# v4_a.net
KiCad netlist of a schematic drawn in EasyEDA Pro
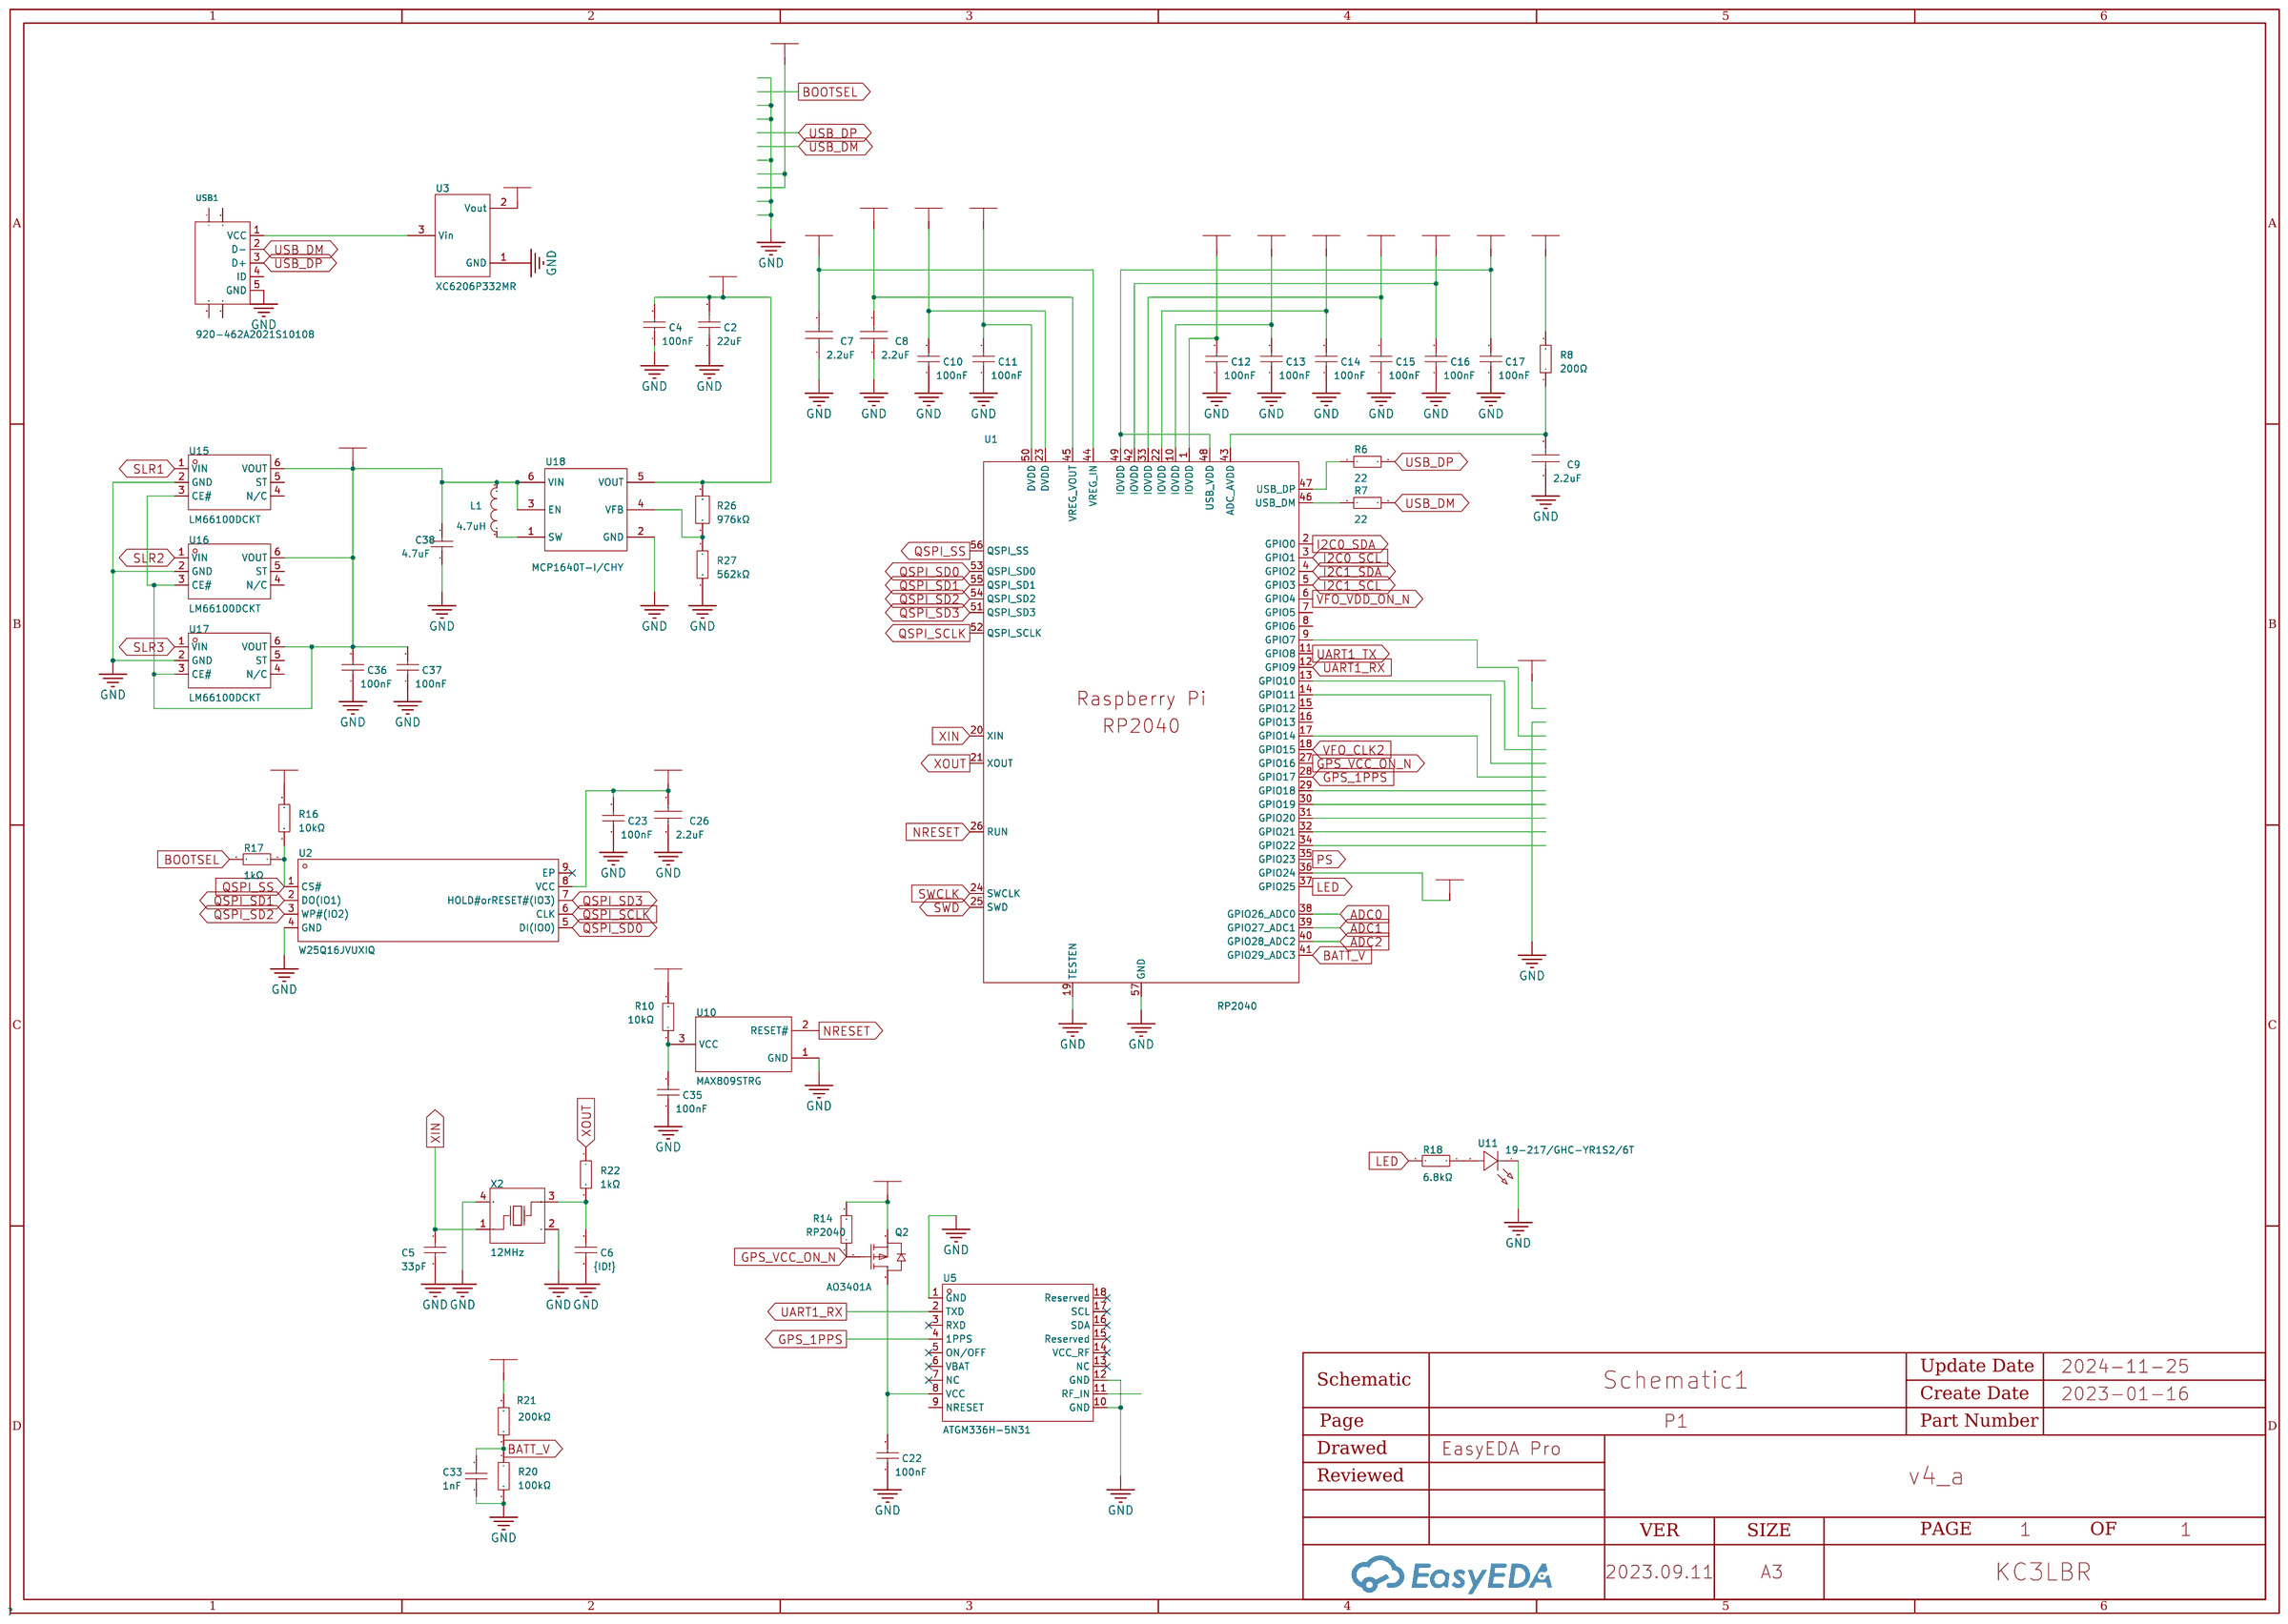
[diagram p0: schematic sheet]

(export (version "E")
  (design (tool "Eeschema 10.0.6"))
  (components
    (comp (ref "C2")
      (value "22uF")
      (footprint "easyedapro:C0603")
      (fields
        (field (name "Manufacturer Part") "CL10A226MQ8NRNC")
        (field (name "Manufacturer") "SAMSUNG(三星)")
      )
      (libsource (lib "easyedapro") (part "CL10A226MQ8NRNC"))
    )
    (comp (ref "C4")
      (value "100nF")
      (footprint "easyedapro:C0402_NEW")
      (fields
        (field (name "Manufacturer Part") "CL05B104KO5NNNC")
        (field (name "Manufacturer") "SAMSUNG(三星)")
      )
      (libsource (lib "easyedapro") (part "CL05B104KO5NNNC"))
    )
    (comp (ref "C5")
      (value "33pF")
      (footprint "easyedapro:C0402")
      (fields (field (name "Manufacturer Part") "0402CG330J500NT") (field (name "Manufacturer") "FH(风华)"))
      (libsource (lib "easyedapro") (part "0402CG330J500NT"))
    )
    (comp (ref "C6")
      (value "33pF")
      (footprint "easyedapro:C0402")
      (fields (field (name "Manufacturer Part") "0402CG330J500NT") (field (name "Manufacturer") "FH(风华)"))
      (libsource (lib "easyedapro") (part "0402CG330J500NT"))
    )
    (comp (ref "C7")
      (value "2.2uF")
      (footprint "easyedapro:C0402")
      (fields
        (field (name "Manufacturer Part") "CL05A225MQ5NSNC")
        (field (name "Manufacturer") "SAMSUNG(三星)")
      )
      (libsource (lib "easyedapro") (part "CL05A225MQ5NSNC"))
    )
    (comp (ref "C8")
      (value "2.2uF")
      (footprint "easyedapro:C0402")
      (fields
        (field (name "Manufacturer Part") "CL05A225MQ5NSNC")
        (field (name "Manufacturer") "SAMSUNG(三星)")
      )
      (libsource (lib "easyedapro") (part "CL05A225MQ5NSNC"))
    )
    (comp (ref "C9")
      (value "2.2uF")
      (footprint "easyedapro:C0402")
      (fields
        (field (name "Manufacturer Part") "CL05A225MQ5NSNC")
        (field (name "Manufacturer") "SAMSUNG(三星)")
      )
      (libsource (lib "easyedapro") (part "CL05A225MQ5NSNC"))
    )
    (comp (ref "C10")
      (value "100nF")
      (footprint "easyedapro:C0402_NEW")
      (fields
        (field (name "Manufacturer Part") "CL05B104KO5NNNC")
        (field (name "Manufacturer") "SAMSUNG(三星)")
      )
      (libsource (lib "easyedapro") (part "CL05B104KO5NNNC"))
    )
    (comp (ref "C11")
      (value "100nF")
      (footprint "easyedapro:C0402_NEW")
      (fields
        (field (name "Manufacturer Part") "CL05B104KO5NNNC")
        (field (name "Manufacturer") "SAMSUNG(三星)")
      )
      (libsource (lib "easyedapro") (part "CL05B104KO5NNNC"))
    )
    (comp (ref "C12")
      (value "100nF")
      (footprint "easyedapro:C0402_NEW")
      (fields
        (field (name "Manufacturer Part") "CL05B104KO5NNNC")
        (field (name "Manufacturer") "SAMSUNG(三星)")
      )
      (libsource (lib "easyedapro") (part "CL05B104KO5NNNC"))
    )
    (comp (ref "C13")
      (value "100nF")
      (footprint "easyedapro:C0402_NEW")
      (fields
        (field (name "Manufacturer Part") "CL05B104KO5NNNC")
        (field (name "Manufacturer") "SAMSUNG(三星)")
      )
      (libsource (lib "easyedapro") (part "CL05B104KO5NNNC"))
    )
    (comp (ref "C14")
      (value "100nF")
      (footprint "easyedapro:C0402_NEW")
      (fields
        (field (name "Manufacturer Part") "CL05B104KO5NNNC")
        (field (name "Manufacturer") "SAMSUNG(三星)")
      )
      (libsource (lib "easyedapro") (part "CL05B104KO5NNNC"))
    )
    (comp (ref "C15")
      (value "100nF")
      (footprint "easyedapro:C0402_NEW")
      (fields
        (field (name "Manufacturer Part") "CL05B104KO5NNNC")
        (field (name "Manufacturer") "SAMSUNG(三星)")
      )
      (libsource (lib "easyedapro") (part "CL05B104KO5NNNC"))
    )
    (comp (ref "C16")
      (value "100nF")
      (footprint "easyedapro:C0402_NEW")
      (fields
        (field (name "Manufacturer Part") "CL05B104KO5NNNC")
        (field (name "Manufacturer") "SAMSUNG(三星)")
      )
      (libsource (lib "easyedapro") (part "CL05B104KO5NNNC"))
    )
    (comp (ref "C17")
      (value "100nF")
      (footprint "easyedapro:C0402_NEW")
      (fields
        (field (name "Manufacturer Part") "CL05B104KO5NNNC")
        (field (name "Manufacturer") "SAMSUNG(三星)")
      )
      (libsource (lib "easyedapro") (part "CL05B104KO5NNNC"))
    )
    (comp (ref "C22")
      (value "100nF")
      (footprint "easyedapro:C0402_NEW")
      (fields
        (field (name "Manufacturer Part") "CL05B104KO5NNNC")
        (field (name "Manufacturer") "SAMSUNG(三星)")
      )
      (libsource (lib "easyedapro") (part "CL05B104KO5NNNC"))
    )
    (comp (ref "C23")
      (value "100nF")
      (footprint "easyedapro:C0402_NEW")
      (fields
        (field (name "Manufacturer Part") "CL05B104KO5NNNC")
        (field (name "Manufacturer") "SAMSUNG(三星)")
      )
      (libsource (lib "easyedapro") (part "CL05B104KO5NNNC"))
    )
    (comp (ref "C26")
      (value "2.2uF")
      (footprint "easyedapro:C0402")
      (fields
        (field (name "Manufacturer Part") "CL05A225MQ5NSNC")
        (field (name "Manufacturer") "SAMSUNG(三星)")
      )
      (libsource (lib "easyedapro") (part "CL05A225MQ5NSNC"))
    )
    (comp (ref "C33")
      (value "1nF")
      (footprint "easyedapro:C0402")
      (fields (field (name "Manufacturer Part") "0402B102K500NT") (field (name "Manufacturer") "FH(风华)"))
      (libsource (lib "easyedapro") (part "0402B102K500NT"))
    )
    (comp (ref "C35")
      (value "100nF")
      (footprint "easyedapro:C0402_NEW")
      (fields
        (field (name "Manufacturer Part") "CL05B104KO5NNNC")
        (field (name "Manufacturer") "SAMSUNG(三星)")
      )
      (libsource (lib "easyedapro") (part "CL05B104KO5NNNC"))
    )
    (comp (ref "C36")
      (value "100nF")
      (footprint "easyedapro:C0402_NEW")
      (fields
        (field (name "Manufacturer Part") "CL05B104KO5NNNC")
        (field (name "Manufacturer") "SAMSUNG(三星)")
      )
      (libsource (lib "easyedapro") (part "CL05B104KO5NNNC"))
    )
    (comp (ref "C37")
      (value "100nF")
      (footprint "easyedapro:C0402_NEW")
      (fields
        (field (name "Manufacturer Part") "CL05B104KO5NNNC")
        (field (name "Manufacturer") "SAMSUNG(三星)")
      )
      (libsource (lib "easyedapro") (part "CL05B104KO5NNNC"))
    )
    (comp (ref "C38")
      (value "4.7uF")
      (footprint "easyedapro:C0603")
      (fields
        (field (name "Manufacturer Part") "CL10A475KO8NNNC")
        (field (name "Manufacturer") "SAMSUNG(三星)")
      )
      (libsource (lib "easyedapro") (part "CL10A475KO8NNNC"))
    )
    (comp (ref "L1")
      (value "4.7uH")
      (footprint "easyedapro:IND-SMD_L2.5-W1.8")
      (fields
        (field (name "Manufacturer Part") "CBC2518T4R7M")
        (field (name "Manufacturer") "TAIYO YUDEN(太诱)")
      )
      (libsource (lib "easyedapro") (part "CBC2518T4R7M"))
    )
    (comp (ref "Q2")
      (value "AO3401A")
      (footprint "easyedapro:SOT-23_L2.9-W1.3-P1.90-LS2.4-BR")
      (fields (field (name "Manufacturer") "AOS"))
      (libsource (lib "easyedapro") (part "AO3401A"))
    )
    (comp (ref "R6")
      (value "22")
      (footprint "easyedapro:R0402")
      (fields
        (field (name "Manufacturer Part") "0402WGF220JTCE")
        (field (name "Manufacturer") "UNI-ROYAL(厚声)")
      )
      (libsource (lib "easyedapro") (part "0402WGF220JTCE"))
    )
    (comp (ref "R7")
      (value "22")
      (footprint "easyedapro:R0402")
      (fields
        (field (name "Manufacturer Part") "0402WGF220JTCE")
        (field (name "Manufacturer") "UNI-ROYAL(厚声)")
      )
      (libsource (lib "easyedapro") (part "0402WGF220JTCE"))
    )
    (comp (ref "R8")
      (value "200Ω")
      (footprint "easyedapro:R0402")
      (fields
        (field (name "Manufacturer Part") "0402WGF2000TCE")
        (field (name "Manufacturer") "UNI-ROYAL(厚声)")
      )
      (libsource (lib "easyedapro") (part "0402WGF2000TCE"))
    )
    (comp (ref "R10")
      (value "10kΩ")
      (footprint "easyedapro:R0402")
      (fields
        (field (name "Manufacturer Part") "0402WGF1002TCE")
        (field (name "Manufacturer") "UNI-ROYAL(厚声)")
      )
      (libsource (lib "easyedapro") (part "0402WGF1002TCE"))
    )
    (comp (ref "R14")
      (value "RP2040")
      (footprint "easyedapro:R0402")
      (fields (field (name "Manufacturer") "Raspberry Pi(树莓派)"))
      (libsource (lib "easyedapro") (part "0402WGF1002TCE"))
    )
    (comp (ref "R16")
      (value "10kΩ")
      (footprint "easyedapro:R0402")
      (fields
        (field (name "Manufacturer Part") "0402WGF1002TCE")
        (field (name "Manufacturer") "UNI-ROYAL(厚声)")
      )
      (libsource (lib "easyedapro") (part "0402WGF1002TCE"))
    )
    (comp (ref "R17")
      (value "1kΩ")
      (footprint "easyedapro:R0402")
      (fields
        (field (name "Manufacturer Part") "0402WGF1001TCE")
        (field (name "Manufacturer") "UNI-ROYAL(厚声)")
      )
      (libsource (lib "easyedapro") (part "0402WGF1001TCE"))
    )
    (comp (ref "R18")
      (value "6.8kΩ")
      (footprint "easyedapro:R0402")
      (fields
        (field (name "Manufacturer Part") "0402WGF6801TCE")
        (field (name "Manufacturer") "UNI-ROYAL(厚声)")
      )
      (libsource (lib "easyedapro") (part "0402WGF6801TCE"))
    )
    (comp (ref "R20")
      (value "100kΩ")
      (footprint "easyedapro:R0402")
      (fields
        (field (name "Manufacturer Part") "0402WGF1003TCE")
        (field (name "Manufacturer") "UNI-ROYAL(厚声)")
      )
      (libsource (lib "easyedapro") (part "0402WGF1003TCE"))
    )
    (comp (ref "R21")
      (value "200kΩ")
      (footprint "easyedapro:R0402")
      (fields
        (field (name "Manufacturer Part") "0402WGF2003TCE")
        (field (name "Manufacturer") "UNI-ROYAL(厚声)")
      )
      (libsource (lib "easyedapro") (part "0402WGF2003TCE"))
    )
    (comp (ref "R22")
      (value "1kΩ")
      (footprint "easyedapro:R0402")
      (fields
        (field (name "Manufacturer Part") "0402WGF1001TCE")
        (field (name "Manufacturer") "UNI-ROYAL(厚声)")
      )
      (libsource (lib "easyedapro") (part "0402WGF1001TCE"))
    )
    (comp (ref "R26")
      (value "976kΩ")
      (footprint "easyedapro:R0402")
      (fields (field (name "Manufacturer Part") "RC0402FR-07976KL") (field (name "Manufacturer") "YAGEO(国巨)"))
      (libsource (lib "easyedapro") (part "RC0402FR-07976KL"))
    )
    (comp (ref "R27")
      (value "562kΩ")
      (footprint "easyedapro:R0402")
      (fields (field (name "Manufacturer Part") "RC0402FR-07562KL") (field (name "Manufacturer") "YAGEO(国巨)"))
      (libsource (lib "easyedapro") (part "RC0402FR-07562KL"))
    )
    (comp (ref "U1")
      (value "RP2040")
      (footprint "easyedapro:LQFN-56_L7.0-W7.0-P0.4-EP")
      (fields (field (name "Manufacturer") "Raspberry Pi(树莓派)"))
      (libsource (lib "easyedapro") (part "RP2040"))
    )
    (comp (ref "U2")
      (value "W25Q16JVUXIQ")
      (footprint "easyedapro:USON-8_L3.0-W2.0-P0.50-BL-EP")
      (fields (field (name "Manufacturer") "WINBOND(华邦)"))
      (libsource (lib "easyedapro") (part "W25Q16JVUXIQ"))
    )
    (comp (ref "U3")
      (value "XC6206P332MR")
      (footprint "easyedapro:SOT-23-3_L2.9-W1.6-P1.90-LS2.8-BR")
      (fields (field (name "Manufacturer") "GOODWORK(固得沃克)"))
      (libsource (lib "easyedapro") (part "XC6206P332MR"))
    )
    (comp (ref "U5")
      (value "ATGM336H-5N31")
      (footprint "easyedapro:GPSM-SMD_ATGM336H-TR")
      (fields (field (name "Manufacturer") "杭州中科微"))
      (libsource (lib "easyedapro") (part "ATGM336H-5N31"))
    )
    (comp (ref "U10")
      (value "MAX809STRG")
      (footprint "easyedapro:SOT-23-3_L2.9-W1.6-P1.90-LS2.8-BR")
      (fields (field (name "Manufacturer") "onsemi(安森美)"))
      (libsource (lib "easyedapro") (part "MAX809STRG"))
    )
    (comp (ref "U11")
      (value "19-217/GHC-YR1S2/6T")
      (footprint "easyedapro:LED0603-RD_GREEN")
      (fields (field (name "Manufacturer") "EVERLIGHT(亿光)"))
      (libsource (lib "easyedapro") (part "19-217/GHC-YR1S2/6T"))
    )
    (comp (ref "U15")
      (value "LM66100DCKT")
      (footprint "easyedapro:SC-70-6_L2.0-W1.3-P0.65-LS2.1-BL")
      (fields (field (name "Manufacturer") "TI(德州仪器)"))
      (libsource (lib "easyedapro") (part "LM66100DCKT"))
    )
    (comp (ref "U16")
      (value "LM66100DCKT")
      (footprint "easyedapro:SC-70-6_L2.0-W1.3-P0.65-LS2.1-BL")
      (fields (field (name "Manufacturer") "TI(德州仪器)"))
      (libsource (lib "easyedapro") (part "LM66100DCKT"))
    )
    (comp (ref "U17")
      (value "LM66100DCKT")
      (footprint "easyedapro:SC-70-6_L2.0-W1.3-P0.65-LS2.1-BL")
      (fields (field (name "Manufacturer") "TI(德州仪器)"))
      (libsource (lib "easyedapro") (part "LM66100DCKT"))
    )
    (comp (ref "U18")
      (value "MCP1640T-I/CHY")
      (footprint "easyedapro:SOT-23-6_L2.9-W1.6-P0.95-LS2.8-BR")
      (fields (field (name "Manufacturer") "MICROCHIP(美国微芯)"))
      (libsource (lib "easyedapro") (part "MCP1640T-I/CHY"))
    )
    (comp (ref "USB1")
      (value "920-462A2021S10108")
      (footprint "easyedapro:MINI-USB-SMD_C105424")
      (description "Connector Type:Mini-B Standard:USB 2.0 Gender:Female Number of Ports:1 Number of Contacts:5P")
      (fields (field (name "Manufacturer") "精拓金"))
      (libsource (lib "easyedapro") (part "USB-MINI-SMD-9.2X9.4-H3.7"))
    )
    (comp (ref "X2")
      (value "12MHz")
      (footprint "easyedapro:OSC-SMD_4P-L3.2-W2.5-BL")
      (fields (field (name "Manufacturer Part") "X322512MSB4SI") (field (name "Manufacturer") "YXC(扬兴晶振)"))
      (libsource (lib "easyedapro") (part "X322512MSB4SI"))
    )
  )
  (nets
    (net (code "1") (name "1V1") (class "Default")
      (node (ref "C10") (pin "2") (pinfunction "2_2") (pintype "input"))
      (node (ref "C11") (pin "2") (pinfunction "2_2") (pintype "input"))
      (node (ref "C8") (pin "2") (pinfunction "2_2") (pintype "input"))
      (node (ref "U1") (pin "23") (pinfunction "DVDD_23") (pintype "bidirectional"))
      (node (ref "U1") (pin "45") (pinfunction "VREG_VOUT_45") (pintype "bidirectional"))
      (node (ref "U1") (pin "50") (pinfunction "DVDD_50") (pintype "bidirectional"))
    )
    (net (code "2") (name "3V3") (class "Default")
      (node (ref "C12") (pin "2") (pinfunction "2_2") (pintype "input"))
      (node (ref "C13") (pin "2") (pinfunction "2_2") (pintype "input"))
      (node (ref "C14") (pin "2") (pinfunction "2_2") (pintype "input"))
      (node (ref "C15") (pin "2") (pinfunction "2_2") (pintype "input"))
      (node (ref "C16") (pin "2") (pinfunction "2_2") (pintype "input"))
      (node (ref "C17") (pin "2") (pinfunction "2_2") (pintype "input"))
      (node (ref "C2") (pin "2") (pinfunction "2_2") (pintype "input"))
      (node (ref "C23") (pin "2") (pinfunction "2_2") (pintype "input"))
      (node (ref "C26") (pin "2") (pinfunction "2_2") (pintype "input"))
      (node (ref "C4") (pin "2") (pinfunction "2_2") (pintype "input"))
      (node (ref "C7") (pin "2") (pinfunction "2_2") (pintype "input"))
      (node (ref "Q2") (pin "2") (pinfunction "S_2") (pintype "input"))
      (node (ref "R10") (pin "2") (pinfunction "2_2") (pintype "input"))
      (node (ref "R14") (pin "2") (pinfunction "2_2") (pintype "input"))
      (node (ref "R16") (pin "2") (pinfunction "2_2") (pintype "input"))
      (node (ref "R26") (pin "2") (pinfunction "2_2") (pintype "unspecified"))
      (node (ref "R8") (pin "2") (pinfunction "2_2") (pintype "input"))
      (node (ref "U1") (pin "1") (pinfunction "IOVDD_1") (pintype "bidirectional"))
      (node (ref "U1") (pin "10") (pinfunction "IOVDD_10") (pintype "bidirectional"))
      (node (ref "U1") (pin "22") (pinfunction "IOVDD_22") (pintype "bidirectional"))
      (node (ref "U1") (pin "33") (pinfunction "IOVDD_33") (pintype "bidirectional"))
      (node (ref "U1") (pin "36") (pinfunction "GPIO24_36") (pintype "bidirectional"))
      (node (ref "U1") (pin "42") (pinfunction "IOVDD_42") (pintype "bidirectional"))
      (node (ref "U1") (pin "44") (pinfunction "VREG_IN_44") (pintype "bidirectional"))
      (node (ref "U1") (pin "48") (pinfunction "USB_VDD_48") (pintype "bidirectional"))
      (node (ref "U1") (pin "49") (pinfunction "IOVDD_49") (pintype "bidirectional"))
      (node (ref "U18") (pin "5") (pinfunction "VOUT_5") (pintype "input"))
      (node (ref "U2") (pin "8") (pinfunction "VCC_8") (pintype "input"))
      (node (ref "U3") (pin "2") (pinfunction "Vout_2") (pintype "input"))
    )
    (net (code "3") (name "ADC0") (class "Default")
      (node (ref "U1") (pin "38") (pinfunction "GPIO26_ADC0_38") (pintype "bidirectional"))
    )
    (net (code "4") (name "ADC1") (class "Default")
      (node (ref "U1") (pin "39") (pinfunction "GPIO27_ADC1_39") (pintype "bidirectional"))
    )
    (net (code "5") (name "ADC2") (class "Default")
      (node (ref "U1") (pin "40") (pinfunction "GPIO28_ADC2_40") (pintype "bidirectional"))
    )
    (net (code "6") (name "BATT_V") (class "Default")
      (node (ref "C33") (pin "2") (pinfunction "2_2") (pintype "input"))
      (node (ref "R20") (pin "1") (pinfunction "1_1") (pintype "input"))
      (node (ref "R21") (pin "1") (pinfunction "1_1") (pintype "input"))
      (node (ref "U1") (pin "41") (pinfunction "GPIO29_ADC3_41") (pintype "bidirectional"))
    )
    (net (code "7") (name "BOOTSEL") (class "Default")
      (node (ref "R17") (pin "2") (pinfunction "2_2") (pintype "input"))
    )
    (net (code "8") (name "GND") (class "Default")
      (node (ref "C10") (pin "1") (pinfunction "1_1") (pintype "input"))
      (node (ref "C11") (pin "1") (pinfunction "1_1") (pintype "input"))
      (node (ref "C12") (pin "1") (pinfunction "1_1") (pintype "input"))
      (node (ref "C13") (pin "1") (pinfunction "1_1") (pintype "input"))
      (node (ref "C14") (pin "1") (pinfunction "1_1") (pintype "input"))
      (node (ref "C15") (pin "1") (pinfunction "1_1") (pintype "input"))
      (node (ref "C16") (pin "1") (pinfunction "1_1") (pintype "input"))
      (node (ref "C17") (pin "1") (pinfunction "1_1") (pintype "input"))
      (node (ref "C2") (pin "1") (pinfunction "1_1") (pintype "input"))
      (node (ref "C22") (pin "1") (pinfunction "1_1") (pintype "input"))
      (node (ref "C23") (pin "1") (pinfunction "1_1") (pintype "input"))
      (node (ref "C26") (pin "1") (pinfunction "1_1") (pintype "input"))
      (node (ref "C33") (pin "1") (pinfunction "1_1") (pintype "input"))
      (node (ref "C35") (pin "1") (pinfunction "1_1") (pintype "input"))
      (node (ref "C36") (pin "1") (pinfunction "1_1") (pintype "input"))
      (node (ref "C37") (pin "1") (pinfunction "1_1") (pintype "input"))
      (node (ref "C38") (pin "1") (pinfunction "1_1") (pintype "input"))
      (node (ref "C4") (pin "1") (pinfunction "1_1") (pintype "input"))
      (node (ref "C5") (pin "1") (pinfunction "1_1") (pintype "input"))
      (node (ref "C6") (pin "1") (pinfunction "1_1") (pintype "input"))
      (node (ref "C7") (pin "1") (pinfunction "1_1") (pintype "input"))
      (node (ref "C8") (pin "1") (pinfunction "1_1") (pintype "input"))
      (node (ref "C9") (pin "1") (pinfunction "1_1") (pintype "input"))
      (node (ref "R20") (pin "2") (pinfunction "2_2") (pintype "input"))
      (node (ref "R27") (pin "1") (pinfunction "1_1") (pintype "unspecified"))
      (node (ref "U1") (pin "19") (pinfunction "TESTEN_19") (pintype "input"))
      (node (ref "U1") (pin "57") (pinfunction "GND_57") (pintype "bidirectional"))
      (node (ref "U10") (pin "1") (pinfunction "GND_1") (pintype "input"))
      (node (ref "U11") (pin "1") (pinfunction "K_1") (pintype "unspecified"))
      (node (ref "U15") (pin "2") (pinfunction "GND_2") (pintype "input"))
      (node (ref "U16") (pin "2") (pinfunction "GND_2") (pintype "input"))
      (node (ref "U17") (pin "2") (pinfunction "GND_2") (pintype "input"))
      (node (ref "U18") (pin "2") (pinfunction "GND_2") (pintype "input"))
      (node (ref "U2") (pin "4") (pinfunction "GND_4") (pintype "input"))
      (node (ref "U3") (pin "1") (pinfunction "GND_1") (pintype "input"))
      (node (ref "U5") (pin "1") (pinfunction "GND_1") (pintype "input"))
      (node (ref "U5") (pin "10") (pinfunction "GND_10") (pintype "input"))
      (node (ref "U5") (pin "12") (pinfunction "GND_12") (pintype "input"))
      (node (ref "USB1") (pin "5") (pinfunction "GND_5") (pintype "input"))
      (node (ref "X2") (pin "2") (pinfunction "GND_2") (pintype "input"))
      (node (ref "X2") (pin "4") (pinfunction "GND_4") (pintype "input"))
    )
    (net (code "9") (name "GPS_1PPS") (class "Default")
      (node (ref "U1") (pin "28") (pinfunction "GPIO17_28") (pintype "bidirectional"))
      (node (ref "U5") (pin "4") (pinfunction "1PPS_4") (pintype "input"))
    )
    (net (code "10") (name "GPS_VCC_ON_N") (class "Default")
      (node (ref "Q2") (pin "1") (pinfunction "G_1") (pintype "input"))
      (node (ref "R14") (pin "1") (pinfunction "1_1") (pintype "input"))
      (node (ref "U1") (pin "27") (pinfunction "GPIO16_27") (pintype "bidirectional"))
    )
    (net (code "11") (name "I2C0_SCL") (class "Default")
      (node (ref "U1") (pin "3") (pinfunction "GPIO1_3") (pintype "bidirectional"))
    )
    (net (code "12") (name "I2C0_SDA") (class "Default")
      (node (ref "U1") (pin "2") (pinfunction "GPIO0_2") (pintype "bidirectional"))
    )
    (net (code "13") (name "I2C1_SCL") (class "Default")
      (node (ref "U1") (pin "5") (pinfunction "GPIO3_5") (pintype "bidirectional"))
    )
    (net (code "14") (name "I2C1_SDA") (class "Default")
      (node (ref "U1") (pin "4") (pinfunction "GPIO2_4") (pintype "bidirectional"))
    )
    (net (code "15") (name "LED") (class "Default")
      (node (ref "R18") (pin "2") (pinfunction "2_2") (pintype "input"))
      (node (ref "U1") (pin "37") (pinfunction "GPIO25_37") (pintype "bidirectional"))
    )
    (net (code "16") (name "NRESET") (class "Default")
      (node (ref "U1") (pin "26") (pinfunction "RUN_26") (pintype "input"))
      (node (ref "U10") (pin "2") (pinfunction "RESET#_2") (pintype "input"))
    )
    (net (code "17") (name "Net-(Q2-D)") (class "Default")
      (node (ref "C22") (pin "2") (pinfunction "2_2") (pintype "input"))
      (node (ref "Q2") (pin "3") (pinfunction "D_3") (pintype "input"))
      (node (ref "U5") (pin "8") (pinfunction "VCC_8") (pintype "input"))
    )
    (net (code "18") (name "Net-(U1-ADC_AVDD)") (class "Default")
      (node (ref "C9") (pin "2") (pinfunction "2_2") (pintype "input"))
      (node (ref "R8") (pin "1") (pinfunction "1_1") (pintype "input"))
      (node (ref "U1") (pin "43") (pinfunction "ADC_AVDD_43") (pintype "bidirectional"))
    )
    (net (code "19") (name "Net-(U1-USB_DM)") (class "Default")
      (node (ref "R7") (pin "1") (pinfunction "1_1") (pintype "input"))
      (node (ref "U1") (pin "46") (pinfunction "USB_DM_46") (pintype "bidirectional"))
    )
    (net (code "20") (name "Net-(U1-USB_DP)") (class "Default")
      (node (ref "R6") (pin "1") (pinfunction "1_1") (pintype "input"))
      (node (ref "U1") (pin "47") (pinfunction "USB_DP_47") (pintype "bidirectional"))
    )
    (net (code "21") (name "Net-(U3-Vin)") (class "Default")
      (node (ref "U3") (pin "3") (pinfunction "Vin_3") (pintype "input"))
      (node (ref "USB1") (pin "1") (pinfunction "VCC_1") (pintype "input"))
    )
    (net (code "22") (name "Net-(U10-VCC)") (class "Default")
      (node (ref "C35") (pin "2") (pinfunction "2_2") (pintype "input"))
      (node (ref "R10") (pin "1") (pinfunction "1_1") (pintype "input"))
      (node (ref "U10") (pin "3") (pinfunction "VCC_3") (pintype "input"))
    )
    (net (code "23") (name "Net-(U11-A)") (class "Default")
      (node (ref "R18") (pin "1") (pinfunction "1_1") (pintype "input"))
      (node (ref "U11") (pin "2") (pinfunction "A_2") (pintype "unspecified"))
    )
    (net (code "24") (name "Net-(U18-SW)") (class "Default")
      (node (ref "L1") (pin "1") (pinfunction "1_1") (pintype "input"))
      (node (ref "U18") (pin "1") (pinfunction "SW_1") (pintype "input"))
    )
    (net (code "25") (name "Net-(U18-VFB)") (class "Default")
      (node (ref "R26") (pin "1") (pinfunction "1_1") (pintype "unspecified"))
      (node (ref "R27") (pin "2") (pinfunction "2_2") (pintype "unspecified"))
      (node (ref "U18") (pin "4") (pinfunction "VFB_4") (pintype "input"))
    )
    (net (code "26") (name "Net-(X2-OSC2)") (class "Default")
      (node (ref "C6") (pin "2") (pinfunction "2_2") (pintype "input"))
      (node (ref "R22") (pin "2") (pinfunction "2_2") (pintype "input"))
      (node (ref "X2") (pin "3") (pinfunction "OSC2_3") (pintype "input"))
    )
    (net (code "27") (name "PS") (class "Default")
      (node (ref "U1") (pin "35") (pinfunction "GPIO23_35") (pintype "bidirectional"))
    )
    (net (code "28") (name "QSPI_SCLK") (class "Default")
      (node (ref "U1") (pin "52") (pinfunction "QSPI_SCLK_52") (pintype "output"))
      (node (ref "U2") (pin "6") (pinfunction "CLK_6") (pintype "input"))
    )
    (net (code "29") (name "QSPI_SD0") (class "Default")
      (node (ref "U1") (pin "53") (pinfunction "QSPI_SD0_53") (pintype "bidirectional"))
      (node (ref "U2") (pin "5") (pinfunction "DI(IO0)_5") (pintype "input"))
    )
    (net (code "30") (name "QSPI_SD1") (class "Default")
      (node (ref "U1") (pin "55") (pinfunction "QSPI_SD1_55") (pintype "bidirectional"))
      (node (ref "U2") (pin "2") (pinfunction "DO(IO1)_2") (pintype "input"))
    )
    (net (code "31") (name "QSPI_SD2") (class "Default")
      (node (ref "U1") (pin "54") (pinfunction "QSPI_SD2_54") (pintype "bidirectional"))
      (node (ref "U2") (pin "3") (pinfunction "WP#(IO2)_3") (pintype "input"))
    )
    (net (code "32") (name "QSPI_SD3") (class "Default")
      (node (ref "U1") (pin "51") (pinfunction "QSPI_SD3_51") (pintype "bidirectional"))
      (node (ref "U2") (pin "7") (pinfunction "HOLD#orRESET#(IO3)_7") (pintype "input"))
    )
    (net (code "33") (name "QSPI_SS") (class "Default")
      (node (ref "R16") (pin "1") (pinfunction "1_1") (pintype "input"))
      (node (ref "R17") (pin "1") (pinfunction "1_1") (pintype "input"))
      (node (ref "U1") (pin "56") (pinfunction "QSPI_SS_56") (pintype "bidirectional"))
      (node (ref "U2") (pin "1") (pinfunction "CS#_1") (pintype "input"))
    )
    (net (code "34") (name "SLR1") (class "Default")
      (node (ref "U15") (pin "1") (pinfunction "VIN_1") (pintype "input"))
    )
    (net (code "35") (name "SLR2") (class "Default")
      (node (ref "U16") (pin "1") (pinfunction "VIN_1") (pintype "input"))
    )
    (net (code "36") (name "SLR3") (class "Default")
      (node (ref "U17") (pin "1") (pinfunction "VIN_1") (pintype "input"))
    )
    (net (code "37") (name "SWCLK") (class "Default")
      (node (ref "U1") (pin "24") (pinfunction "SWCLK_24") (pintype "output"))
    )
    (net (code "38") (name "SWD") (class "Default")
      (node (ref "U1") (pin "25") (pinfunction "SWD_25") (pintype "bidirectional"))
    )
    (net (code "39") (name "UART1_RX") (class "Default")
      (node (ref "U1") (pin "12") (pinfunction "GPIO9_12") (pintype "bidirectional"))
      (node (ref "U5") (pin "2") (pinfunction "TXD_2") (pintype "input"))
    )
    (net (code "40") (name "UART1_TX") (class "Default")
      (node (ref "U1") (pin "11") (pinfunction "GPIO8_11") (pintype "bidirectional"))
    )
    (net (code "41") (name "USB_DM") (class "Default")
      (node (ref "R7") (pin "2") (pinfunction "2_2") (pintype "input"))
      (node (ref "USB1") (pin "2") (pinfunction "D-_2") (pintype "input"))
    )
    (net (code "42") (name "USB_DP") (class "Default")
      (node (ref "R6") (pin "2") (pinfunction "2_2") (pintype "input"))
      (node (ref "USB1") (pin "3") (pinfunction "D+_3") (pintype "input"))
    )
    (net (code "43") (name "VBUS") (class "Default")
      (node (ref "C36") (pin "2") (pinfunction "2_2") (pintype "input"))
      (node (ref "C37") (pin "2") (pinfunction "2_2") (pintype "input"))
      (node (ref "C38") (pin "2") (pinfunction "2_2") (pintype "input"))
      (node (ref "L1") (pin "2") (pinfunction "2_2") (pintype "input"))
      (node (ref "R21") (pin "2") (pinfunction "2_2") (pintype "input"))
      (node (ref "U15") (pin "3") (pinfunction "CE#_3") (pintype "input"))
      (node (ref "U15") (pin "6") (pinfunction "VOUT_6") (pintype "input"))
      (node (ref "U16") (pin "3") (pinfunction "CE#_3") (pintype "input"))
      (node (ref "U16") (pin "6") (pinfunction "VOUT_6") (pintype "input"))
      (node (ref "U17") (pin "3") (pinfunction "CE#_3") (pintype "input"))
      (node (ref "U17") (pin "6") (pinfunction "VOUT_6") (pintype "input"))
      (node (ref "U18") (pin "3") (pinfunction "EN_3") (pintype "input"))
      (node (ref "U18") (pin "6") (pinfunction "VIN_6") (pintype "input"))
    )
    (net (code "44") (name "VFO_CLK2") (class "Default")
      (node (ref "U1") (pin "18") (pinfunction "GPIO15_18") (pintype "bidirectional"))
    )
    (net (code "45") (name "VFO_VDD_ON_N") (class "Default")
      (node (ref "U1") (pin "6") (pinfunction "GPIO4_6") (pintype "bidirectional"))
    )
    (net (code "46") (name "XIN") (class "Default")
      (node (ref "C5") (pin "2") (pinfunction "2_2") (pintype "input"))
      (node (ref "U1") (pin "20") (pinfunction "XIN_20") (pintype "input"))
      (node (ref "X2") (pin "1") (pinfunction "OSC1_1") (pintype "input"))
    )
    (net (code "47") (name "XOUT") (class "Default")
      (node (ref "R22") (pin "1") (pinfunction "1_1") (pintype "input"))
      (node (ref "U1") (pin "21") (pinfunction "XOUT_21") (pintype "input"))
    )
    (net (code "48") (name "unconnected-(U1-GPIO5-Pad7)") (class "Default")
      (node (ref "U1") (pin "7") (pinfunction "GPIO5_7") (pintype "bidirectional"))
    )
    (net (code "49") (name "unconnected-(U1-GPIO6-Pad8)") (class "Default")
      (node (ref "U1") (pin "8") (pinfunction "GPIO6_8") (pintype "bidirectional"))
    )
    (net (code "50") (name "unconnected-(U1-GPIO7-Pad9)") (class "Default")
      (node (ref "U1") (pin "9") (pinfunction "GPIO7_9") (pintype "bidirectional"))
    )
    (net (code "51") (name "unconnected-(U1-GPIO10-Pad13)") (class "Default")
      (node (ref "U1") (pin "13") (pinfunction "GPIO10_13") (pintype "bidirectional"))
    )
    (net (code "52") (name "unconnected-(U1-GPIO11-Pad14)") (class "Default")
      (node (ref "U1") (pin "14") (pinfunction "GPIO11_14") (pintype "bidirectional"))
    )
    (net (code "53") (name "unconnected-(U1-GPIO12-Pad15)") (class "Default")
      (node (ref "U1") (pin "15") (pinfunction "GPIO12_15") (pintype "bidirectional"))
    )
    (net (code "54") (name "unconnected-(U1-GPIO13-Pad16)") (class "Default")
      (node (ref "U1") (pin "16") (pinfunction "GPIO13_16") (pintype "bidirectional"))
    )
    (net (code "55") (name "unconnected-(U1-GPIO14-Pad17)") (class "Default")
      (node (ref "U1") (pin "17") (pinfunction "GPIO14_17") (pintype "bidirectional"))
    )
    (net (code "56") (name "unconnected-(U1-GPIO18-Pad29)") (class "Default")
      (node (ref "U1") (pin "29") (pinfunction "GPIO18_29") (pintype "bidirectional"))
    )
    (net (code "57") (name "unconnected-(U1-GPIO19-Pad30)") (class "Default")
      (node (ref "U1") (pin "30") (pinfunction "GPIO19_30") (pintype "bidirectional"))
    )
    (net (code "58") (name "unconnected-(U1-GPIO20-Pad31)") (class "Default")
      (node (ref "U1") (pin "31") (pinfunction "GPIO20_31") (pintype "bidirectional"))
    )
    (net (code "59") (name "unconnected-(U1-GPIO21-Pad32)") (class "Default")
      (node (ref "U1") (pin "32") (pinfunction "GPIO21_32") (pintype "bidirectional"))
    )
    (net (code "60") (name "unconnected-(U1-GPIO22-Pad34)") (class "Default")
      (node (ref "U1") (pin "34") (pinfunction "GPIO22_34") (pintype "bidirectional"))
    )
    (net (code "61") (name "unconnected-(U2-EP-Pad9)") (class "Default")
      (node (ref "U2") (pin "9") (pinfunction "EP_9") (pintype "input+no_connect"))
    )
    (net (code "62") (name "unconnected-(U5-NC-Pad7)") (class "Default")
      (node (ref "U5") (pin "7") (pinfunction "NC_7") (pintype "input+no_connect"))
    )
    (net (code "63") (name "unconnected-(U5-NC-Pad13)") (class "Default")
      (node (ref "U5") (pin "13") (pinfunction "NC_13") (pintype "input+no_connect"))
    )
    (net (code "64") (name "unconnected-(U5-NRESET-Pad9)") (class "Default")
      (node (ref "U5") (pin "9") (pinfunction "NRESET_9") (pintype "input"))
    )
    (net (code "65") (name "unconnected-(U5-ON{slash}OFF-Pad5)") (class "Default")
      (node (ref "U5") (pin "5") (pinfunction "ON/OFF_5") (pintype "input+no_connect"))
    )
    (net (code "66") (name "unconnected-(U5-RF_IN-Pad11)") (class "Default")
      (node (ref "U5") (pin "11") (pinfunction "RF_IN_11") (pintype "input"))
    )
    (net (code "67") (name "unconnected-(U5-RXD-Pad3)") (class "Default")
      (node (ref "U5") (pin "3") (pinfunction "RXD_3") (pintype "input+no_connect"))
    )
    (net (code "68") (name "unconnected-(U5-Reserved-Pad15)") (class "Default")
      (node (ref "U5") (pin "15") (pinfunction "Reserved_15") (pintype "input+no_connect"))
    )
    (net (code "69") (name "unconnected-(U5-Reserved-Pad18)") (class "Default")
      (node (ref "U5") (pin "18") (pinfunction "Reserved_18") (pintype "input+no_connect"))
    )
    (net (code "70") (name "unconnected-(U5-SCL-Pad17)") (class "Default")
      (node (ref "U5") (pin "17") (pinfunction "SCL_17") (pintype "input+no_connect"))
    )
    (net (code "71") (name "unconnected-(U5-SDA-Pad16)") (class "Default")
      (node (ref "U5") (pin "16") (pinfunction "SDA_16") (pintype "input+no_connect"))
    )
    (net (code "72") (name "unconnected-(U5-VBAT-Pad6)") (class "Default")
      (node (ref "U5") (pin "6") (pinfunction "VBAT_6") (pintype "input+no_connect"))
    )
    (net (code "73") (name "unconnected-(U5-VCC_RF-Pad14)") (class "Default")
      (node (ref "U5") (pin "14") (pinfunction "VCC_RF_14") (pintype "input+no_connect"))
    )
    (net (code "74") (name "unconnected-(U15-N{slash}C-Pad4)") (class "Default")
      (node (ref "U15") (pin "4") (pinfunction "N/C_4") (pintype "input"))
    )
    (net (code "75") (name "unconnected-(U15-ST-Pad5)") (class "Default")
      (node (ref "U15") (pin "5") (pinfunction "ST_5") (pintype "input"))
    )
    (net (code "76") (name "unconnected-(U16-N{slash}C-Pad4)") (class "Default")
      (node (ref "U16") (pin "4") (pinfunction "N/C_4") (pintype "input"))
    )
    (net (code "77") (name "unconnected-(U16-ST-Pad5)") (class "Default")
      (node (ref "U16") (pin "5") (pinfunction "ST_5") (pintype "input"))
    )
    (net (code "78") (name "unconnected-(U17-N{slash}C-Pad4)") (class "Default")
      (node (ref "U17") (pin "4") (pinfunction "N/C_4") (pintype "input"))
    )
    (net (code "79") (name "unconnected-(U17-ST-Pad5)") (class "Default")
      (node (ref "U17") (pin "5") (pinfunction "ST_5") (pintype "input"))
    )
    (net (code "80") (name "unconnected-(USB1-ID-Pad4)") (class "Default")
      (node (ref "USB1") (pin "4") (pinfunction "ID_4") (pintype "input"))
    )
    (net (code "81") (name "unconnected-(USB1-Pad6)") (class "Default")
      (node (ref "USB1") (pin "6") (pinfunction "6_6") (pintype "input"))
    )
    (net (code "82") (name "unconnected-(USB1-Pad7)") (class "Default")
      (node (ref "USB1") (pin "7") (pinfunction "7_7") (pintype "input"))
    )
    (net (code "83") (name "unconnected-(USB1-Pad8)") (class "Default")
      (node (ref "USB1") (pin "8") (pinfunction "8_8") (pintype "input"))
    )
    (net (code "84") (name "unconnected-(USB1-Pad9)") (class "Default")
      (node (ref "USB1") (pin "9") (pinfunction "9_9") (pintype "input"))
    )
  )
)
